# Painting.net
KiCad netlist of a schematic drawn in EAGLE
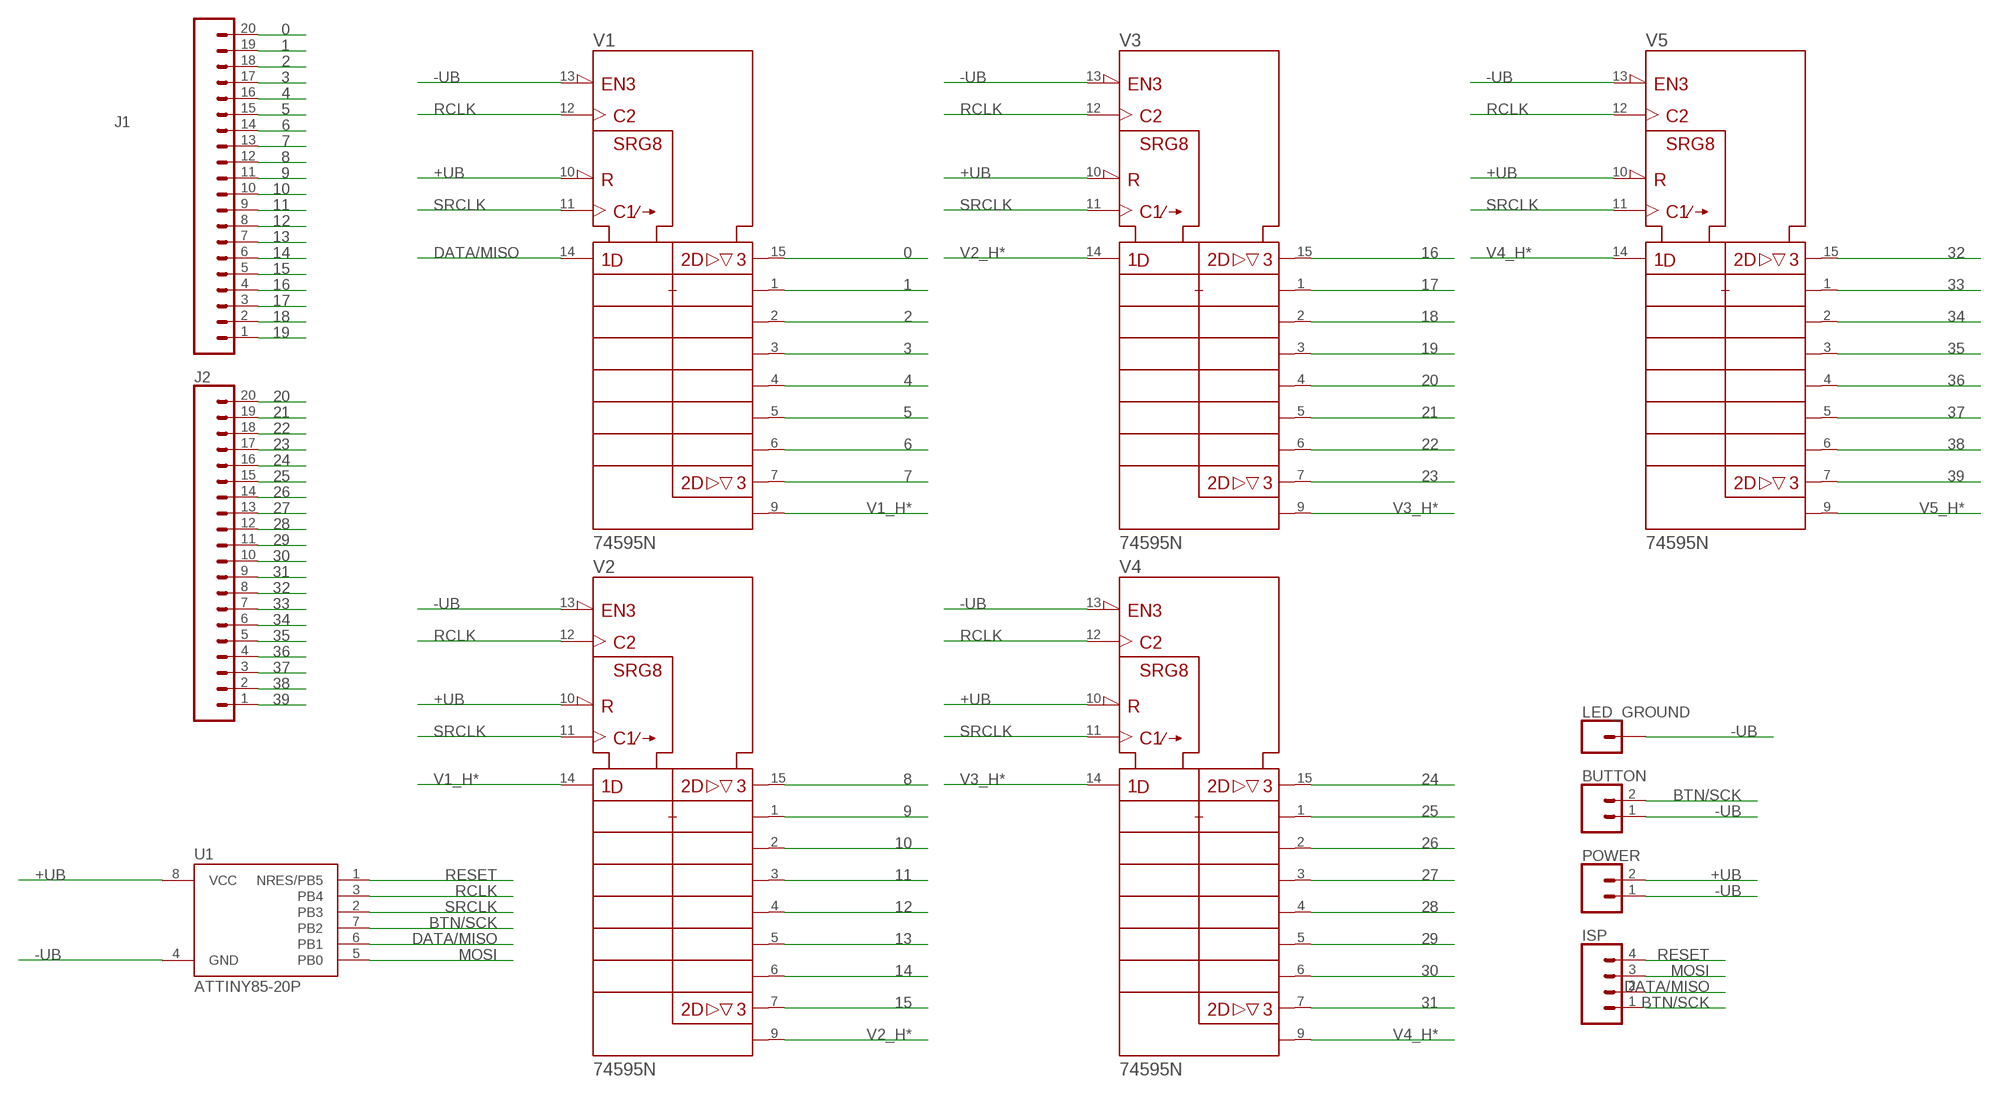
[diagram p0: schematic, sheet 1]

(export (version "E")
  (design (tool "Eeschema 10.0.6"))
  (components
    (comp (ref "BUTTON")
      (value "CONN_02PTH3")
      (footprint "eagle-import:1X02_LONGPADS")
      (libsource (lib "eagle-import") (part "CONN_02PTH3"))
    )
    (comp (ref "ISP")
      (value "CONN_04LONGPADS")
      (footprint "eagle-import:1X04_LONGPADS")
      (libsource (lib "eagle-import") (part "CONN_04LONGPADS"))
    )
    (comp (ref "J1")
      (value "CONN_20")
      (footprint "eagle-import:1X20")
      (libsource (lib "eagle-import") (part "CONN_20"))
    )
    (comp (ref "J2")
      (value "CONN_20")
      (footprint "eagle-import:1X20")
      (libsource (lib "eagle-import") (part "CONN_20"))
    )
    (comp (ref "LED_GROUND")
      (value "CONN_01PTH_LONGPAD")
      (footprint "eagle-import:1X01_LONGPAD")
      (libsource (lib "eagle-import") (part "CONN_01PTH_LONGPAD"))
    )
    (comp (ref "POWER")
      (value "CONN_02PTH3")
      (footprint "eagle-import:1X02_LONGPADS")
      (libsource (lib "eagle-import") (part "CONN_02PTH3"))
    )
    (comp (ref "U1")
      (value "ATTINY85-20P")
      (footprint "eagle-import:PDIP08_300MIL")
      (libsource (lib "eagle-import") (part "ATTINY85P-20"))
    )
    (comp (ref "V1")
      (value "74595N")
      (footprint "eagle-import:DIL16")
      (libsource (lib "eagle-import") (part "74595N"))
    )
    (comp (ref "V2")
      (value "74595N")
      (footprint "eagle-import:DIL16")
      (libsource (lib "eagle-import") (part "74595N"))
    )
    (comp (ref "V3")
      (value "74595N")
      (footprint "eagle-import:DIL16")
      (libsource (lib "eagle-import") (part "74595N"))
    )
    (comp (ref "V4")
      (value "74595N")
      (footprint "eagle-import:DIL16")
      (libsource (lib "eagle-import") (part "74595N"))
    )
    (comp (ref "V5")
      (value "74595N")
      (footprint "eagle-import:DIL16")
      (libsource (lib "eagle-import") (part "74595N"))
    )
  )
  (nets
    (net (code "1") (name "/+UB") (class "Default")
      (node (ref "POWER") (pin "2") (pinfunction "2_2") (pintype "passive"))
      (node (ref "U1") (pin "8") (pinfunction "VCC_8") (pintype "power_in"))
      (node (ref "V1") (pin "10") (pinfunction "~{SRCLR}_10") (pintype "input"))
      (node (ref "V2") (pin "10") (pinfunction "~{SRCLR}_10") (pintype "input"))
      (node (ref "V3") (pin "10") (pinfunction "~{SRCLR}_10") (pintype "input"))
      (node (ref "V4") (pin "10") (pinfunction "~{SRCLR}_10") (pintype "input"))
      (node (ref "V5") (pin "10") (pinfunction "~{SRCLR}_10") (pintype "input"))
    )
    (net (code "2") (name "/-UB") (class "Default")
      (node (ref "BUTTON") (pin "1") (pinfunction "1_1") (pintype "passive"))
      (node (ref "LED_GROUND") (pin "1") (pinfunction "1_1") (pintype "passive"))
      (node (ref "POWER") (pin "1") (pinfunction "1_1") (pintype "passive"))
      (node (ref "U1") (pin "4") (pinfunction "GND_4") (pintype "power_in"))
      (node (ref "V1") (pin "13") (pinfunction "~{G}_13") (pintype "input"))
      (node (ref "V2") (pin "13") (pinfunction "~{G}_13") (pintype "input"))
      (node (ref "V3") (pin "13") (pinfunction "~{G}_13") (pintype "input"))
      (node (ref "V4") (pin "13") (pinfunction "~{G}_13") (pintype "input"))
      (node (ref "V5") (pin "13") (pinfunction "~{G}_13") (pintype "input"))
    )
    (net (code "3") (name "/0") (class "Default")
      (node (ref "J1") (pin "20") (pinfunction "20_20") (pintype "passive"))
      (node (ref "V1") (pin "15") (pinfunction "QA_15") (pintype "tri_state"))
    )
    (net (code "4") (name "/1") (class "Default")
      (node (ref "J1") (pin "19") (pinfunction "19_19") (pintype "passive"))
      (node (ref "V1") (pin "1") (pinfunction "QB_1") (pintype "tri_state"))
    )
    (net (code "5") (name "/2") (class "Default")
      (node (ref "J1") (pin "18") (pinfunction "18_18") (pintype "passive"))
      (node (ref "V1") (pin "2") (pinfunction "QC_2") (pintype "tri_state"))
    )
    (net (code "6") (name "/3") (class "Default")
      (node (ref "J1") (pin "17") (pinfunction "17_17") (pintype "passive"))
      (node (ref "V1") (pin "3") (pinfunction "QD_3") (pintype "tri_state"))
    )
    (net (code "7") (name "/4") (class "Default")
      (node (ref "J1") (pin "16") (pinfunction "16_16") (pintype "passive"))
      (node (ref "V1") (pin "4") (pinfunction "QE_4") (pintype "tri_state"))
    )
    (net (code "8") (name "/5") (class "Default")
      (node (ref "J1") (pin "15") (pinfunction "15_15") (pintype "passive"))
      (node (ref "V1") (pin "5") (pinfunction "QF_5") (pintype "tri_state"))
    )
    (net (code "9") (name "/6") (class "Default")
      (node (ref "J1") (pin "14") (pinfunction "14_14") (pintype "passive"))
      (node (ref "V1") (pin "6") (pinfunction "QG_6") (pintype "tri_state"))
    )
    (net (code "10") (name "/7") (class "Default")
      (node (ref "J1") (pin "13") (pinfunction "13_13") (pintype "passive"))
      (node (ref "V1") (pin "7") (pinfunction "QH_7") (pintype "tri_state"))
    )
    (net (code "11") (name "/8") (class "Default")
      (node (ref "J1") (pin "12") (pinfunction "12_12") (pintype "passive"))
      (node (ref "V2") (pin "15") (pinfunction "QA_15") (pintype "tri_state"))
    )
    (net (code "12") (name "/9") (class "Default")
      (node (ref "J1") (pin "11") (pinfunction "11_11") (pintype "passive"))
      (node (ref "V2") (pin "1") (pinfunction "QB_1") (pintype "tri_state"))
    )
    (net (code "13") (name "/10") (class "Default")
      (node (ref "J1") (pin "10") (pinfunction "10_10") (pintype "passive"))
      (node (ref "V2") (pin "2") (pinfunction "QC_2") (pintype "tri_state"))
    )
    (net (code "14") (name "/11") (class "Default")
      (node (ref "J1") (pin "9") (pinfunction "9_9") (pintype "passive"))
      (node (ref "V2") (pin "3") (pinfunction "QD_3") (pintype "tri_state"))
    )
    (net (code "15") (name "/12") (class "Default")
      (node (ref "J1") (pin "8") (pinfunction "8_8") (pintype "passive"))
      (node (ref "V2") (pin "4") (pinfunction "QE_4") (pintype "tri_state"))
    )
    (net (code "16") (name "/13") (class "Default")
      (node (ref "J1") (pin "7") (pinfunction "7_7") (pintype "passive"))
      (node (ref "V2") (pin "5") (pinfunction "QF_5") (pintype "tri_state"))
    )
    (net (code "17") (name "/14") (class "Default")
      (node (ref "J1") (pin "6") (pinfunction "6_6") (pintype "passive"))
      (node (ref "V2") (pin "6") (pinfunction "QG_6") (pintype "tri_state"))
    )
    (net (code "18") (name "/15") (class "Default")
      (node (ref "J1") (pin "5") (pinfunction "5_5") (pintype "passive"))
      (node (ref "V2") (pin "7") (pinfunction "QH_7") (pintype "tri_state"))
    )
    (net (code "19") (name "/16") (class "Default")
      (node (ref "J1") (pin "4") (pinfunction "4_4") (pintype "passive"))
      (node (ref "V3") (pin "15") (pinfunction "QA_15") (pintype "tri_state"))
    )
    (net (code "20") (name "/17") (class "Default")
      (node (ref "J1") (pin "3") (pinfunction "3_3") (pintype "passive"))
      (node (ref "V3") (pin "1") (pinfunction "QB_1") (pintype "tri_state"))
    )
    (net (code "21") (name "/18") (class "Default")
      (node (ref "J1") (pin "2") (pinfunction "2_2") (pintype "passive"))
      (node (ref "V3") (pin "2") (pinfunction "QC_2") (pintype "tri_state"))
    )
    (net (code "22") (name "/19") (class "Default")
      (node (ref "J1") (pin "1") (pinfunction "1_1") (pintype "passive"))
      (node (ref "V3") (pin "3") (pinfunction "QD_3") (pintype "tri_state"))
    )
    (net (code "23") (name "/20") (class "Default")
      (node (ref "J2") (pin "20") (pinfunction "20_20") (pintype "passive"))
      (node (ref "V3") (pin "4") (pinfunction "QE_4") (pintype "tri_state"))
    )
    (net (code "24") (name "/21") (class "Default")
      (node (ref "J2") (pin "19") (pinfunction "19_19") (pintype "passive"))
      (node (ref "V3") (pin "5") (pinfunction "QF_5") (pintype "tri_state"))
    )
    (net (code "25") (name "/22") (class "Default")
      (node (ref "J2") (pin "18") (pinfunction "18_18") (pintype "passive"))
      (node (ref "V3") (pin "6") (pinfunction "QG_6") (pintype "tri_state"))
    )
    (net (code "26") (name "/23") (class "Default")
      (node (ref "J2") (pin "17") (pinfunction "17_17") (pintype "passive"))
      (node (ref "V3") (pin "7") (pinfunction "QH_7") (pintype "tri_state"))
    )
    (net (code "27") (name "/24") (class "Default")
      (node (ref "J2") (pin "16") (pinfunction "16_16") (pintype "passive"))
      (node (ref "V4") (pin "15") (pinfunction "QA_15") (pintype "tri_state"))
    )
    (net (code "28") (name "/25") (class "Default")
      (node (ref "J2") (pin "15") (pinfunction "15_15") (pintype "passive"))
      (node (ref "V4") (pin "1") (pinfunction "QB_1") (pintype "tri_state"))
    )
    (net (code "29") (name "/26") (class "Default")
      (node (ref "J2") (pin "14") (pinfunction "14_14") (pintype "passive"))
      (node (ref "V4") (pin "2") (pinfunction "QC_2") (pintype "tri_state"))
    )
    (net (code "30") (name "/27") (class "Default")
      (node (ref "J2") (pin "13") (pinfunction "13_13") (pintype "passive"))
      (node (ref "V4") (pin "3") (pinfunction "QD_3") (pintype "tri_state"))
    )
    (net (code "31") (name "/28") (class "Default")
      (node (ref "J2") (pin "12") (pinfunction "12_12") (pintype "passive"))
      (node (ref "V4") (pin "4") (pinfunction "QE_4") (pintype "tri_state"))
    )
    (net (code "32") (name "/29") (class "Default")
      (node (ref "J2") (pin "11") (pinfunction "11_11") (pintype "passive"))
      (node (ref "V4") (pin "5") (pinfunction "QF_5") (pintype "tri_state"))
    )
    (net (code "33") (name "/30") (class "Default")
      (node (ref "J2") (pin "10") (pinfunction "10_10") (pintype "passive"))
      (node (ref "V4") (pin "6") (pinfunction "QG_6") (pintype "tri_state"))
    )
    (net (code "34") (name "/31") (class "Default")
      (node (ref "J2") (pin "9") (pinfunction "9_9") (pintype "passive"))
      (node (ref "V4") (pin "7") (pinfunction "QH_7") (pintype "tri_state"))
    )
    (net (code "35") (name "/32") (class "Default")
      (node (ref "J2") (pin "8") (pinfunction "8_8") (pintype "passive"))
      (node (ref "V5") (pin "15") (pinfunction "QA_15") (pintype "tri_state"))
    )
    (net (code "36") (name "/33") (class "Default")
      (node (ref "J2") (pin "7") (pinfunction "7_7") (pintype "passive"))
      (node (ref "V5") (pin "1") (pinfunction "QB_1") (pintype "tri_state"))
    )
    (net (code "37") (name "/34") (class "Default")
      (node (ref "J2") (pin "6") (pinfunction "6_6") (pintype "passive"))
      (node (ref "V5") (pin "2") (pinfunction "QC_2") (pintype "tri_state"))
    )
    (net (code "38") (name "/35") (class "Default")
      (node (ref "J2") (pin "5") (pinfunction "5_5") (pintype "passive"))
      (node (ref "V5") (pin "3") (pinfunction "QD_3") (pintype "tri_state"))
    )
    (net (code "39") (name "/36") (class "Default")
      (node (ref "J2") (pin "4") (pinfunction "4_4") (pintype "passive"))
      (node (ref "V5") (pin "4") (pinfunction "QE_4") (pintype "tri_state"))
    )
    (net (code "40") (name "/37") (class "Default")
      (node (ref "J2") (pin "3") (pinfunction "3_3") (pintype "passive"))
      (node (ref "V5") (pin "5") (pinfunction "QF_5") (pintype "tri_state"))
    )
    (net (code "41") (name "/38") (class "Default")
      (node (ref "J2") (pin "2") (pinfunction "2_2") (pintype "passive"))
      (node (ref "V5") (pin "6") (pinfunction "QG_6") (pintype "tri_state"))
    )
    (net (code "42") (name "/39") (class "Default")
      (node (ref "J2") (pin "1") (pinfunction "1_1") (pintype "passive"))
      (node (ref "V5") (pin "7") (pinfunction "QH_7") (pintype "tri_state"))
    )
    (net (code "43") (name "/BTN{slash}SCK") (class "Default")
      (node (ref "BUTTON") (pin "2") (pinfunction "2_2") (pintype "passive"))
      (node (ref "ISP") (pin "1") (pinfunction "1_1") (pintype "passive"))
      (node (ref "U1") (pin "7") (pinfunction "PB2_7") (pintype "bidirectional"))
    )
    (net (code "44") (name "/DATA{slash}MISO") (class "Default")
      (node (ref "ISP") (pin "2") (pinfunction "2_2") (pintype "passive"))
      (node (ref "U1") (pin "6") (pinfunction "PB1_6") (pintype "bidirectional"))
      (node (ref "V1") (pin "14") (pinfunction "SER_14") (pintype "input"))
    )
    (net (code "45") (name "/MOSI") (class "Default")
      (node (ref "ISP") (pin "3") (pinfunction "3_3") (pintype "passive"))
      (node (ref "U1") (pin "5") (pinfunction "PB0_5") (pintype "bidirectional"))
    )
    (net (code "46") (name "/RCLK") (class "Default")
      (node (ref "U1") (pin "3") (pinfunction "PB4_3") (pintype "bidirectional"))
      (node (ref "V1") (pin "12") (pinfunction "RCK_12") (pintype "input"))
      (node (ref "V2") (pin "12") (pinfunction "RCK_12") (pintype "input"))
      (node (ref "V3") (pin "12") (pinfunction "RCK_12") (pintype "input"))
      (node (ref "V4") (pin "12") (pinfunction "RCK_12") (pintype "input"))
      (node (ref "V5") (pin "12") (pinfunction "RCK_12") (pintype "input"))
    )
    (net (code "47") (name "/RESET") (class "Default")
      (node (ref "ISP") (pin "4") (pinfunction "4_4") (pintype "passive"))
      (node (ref "U1") (pin "1") (pinfunction "NRES/PB5_1") (pintype "bidirectional"))
    )
    (net (code "48") (name "/SRCLK") (class "Default")
      (node (ref "U1") (pin "2") (pinfunction "PB3_2") (pintype "bidirectional"))
      (node (ref "V1") (pin "11") (pinfunction "SRCK_11") (pintype "input"))
      (node (ref "V2") (pin "11") (pinfunction "SRCK_11") (pintype "input"))
      (node (ref "V3") (pin "11") (pinfunction "SRCK_11") (pintype "input"))
      (node (ref "V4") (pin "11") (pinfunction "SRCK_11") (pintype "input"))
      (node (ref "V5") (pin "11") (pinfunction "SRCK_11") (pintype "input"))
    )
    (net (code "49") (name "/V1_H*") (class "Default")
      (node (ref "V1") (pin "9") (pinfunction "QH*_9") (pintype "output"))
      (node (ref "V2") (pin "14") (pinfunction "SER_14") (pintype "input"))
    )
    (net (code "50") (name "/V2_H*") (class "Default")
      (node (ref "V2") (pin "9") (pinfunction "QH*_9") (pintype "output"))
      (node (ref "V3") (pin "14") (pinfunction "SER_14") (pintype "input"))
    )
    (net (code "51") (name "/V3_H*") (class "Default")
      (node (ref "V3") (pin "9") (pinfunction "QH*_9") (pintype "output"))
      (node (ref "V4") (pin "14") (pinfunction "SER_14") (pintype "input"))
    )
    (net (code "52") (name "/V4_H*") (class "Default")
      (node (ref "V4") (pin "9") (pinfunction "QH*_9") (pintype "output"))
      (node (ref "V5") (pin "14") (pinfunction "SER_14") (pintype "input"))
    )
    (net (code "53") (name "/V5_H*") (class "Default")
      (node (ref "V5") (pin "9") (pinfunction "QH*_9") (pintype "output"))
    )
  )
)
